# address_decoder_v1.net
KiCad netlist of a schematic drawn in EAGLE
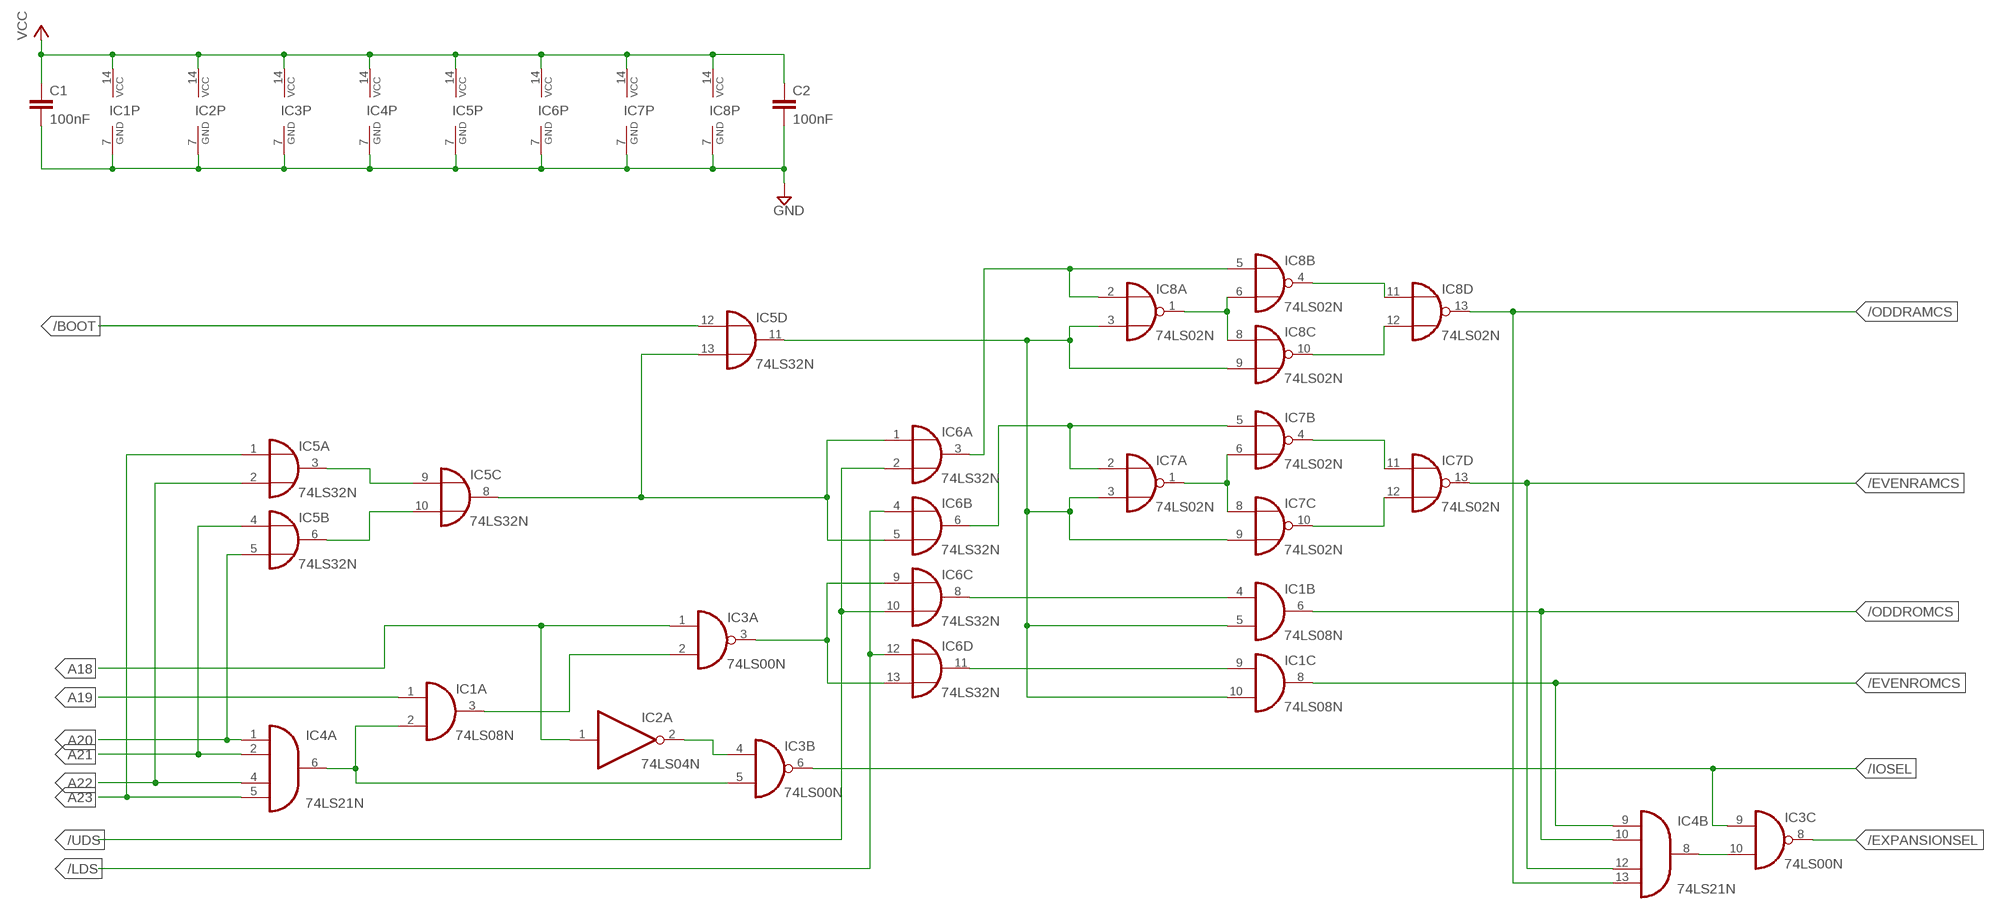
[diagram p0: schematic, sheet 1]

(export (version "E")
  (design (tool "Eeschema 10.0.6"))
  (components
    (comp (ref "C1")
      (value "100nF")
      (footprint "eagle-import:C025-024X044")
      (libsource (lib "eagle-import") (part "C-EU025-024X044"))
    )
    (comp (ref "C2")
      (value "100nF")
      (footprint "eagle-import:C025-024X044")
      (libsource (lib "eagle-import") (part "C-EU025-024X044"))
    )
    (comp (ref "IC1")
      (value "74LS08N")
      (footprint "eagle-import:DIL14")
      (libsource (lib "eagle-import") (part "7408NLS"))
    )
    (comp (ref "IC2")
      (value "74LS04N")
      (footprint "eagle-import:DIL14")
      (libsource (lib "eagle-import") (part "7404NLS"))
    )
    (comp (ref "IC3")
      (value "74LS00N")
      (footprint "eagle-import:DIL14")
      (libsource (lib "eagle-import") (part "7400NLS"))
    )
    (comp (ref "IC4")
      (value "74LS21N")
      (footprint "eagle-import:DIL14")
      (libsource (lib "eagle-import") (part "7421NLS"))
    )
    (comp (ref "IC5")
      (value "74LS32N")
      (footprint "eagle-import:DIL14")
      (libsource (lib "eagle-import") (part "7432NLS"))
    )
    (comp (ref "IC6")
      (value "74LS32N")
      (footprint "eagle-import:DIL14")
      (libsource (lib "eagle-import") (part "7432NLS"))
    )
    (comp (ref "IC7")
      (value "74LS02N")
      (footprint "eagle-import:DIL14")
      (libsource (lib "eagle-import") (part "7402NLS"))
    )
    (comp (ref "IC8")
      (value "74LS02N")
      (footprint "eagle-import:DIL14")
      (libsource (lib "eagle-import") (part "7402NLS"))
    )
  )
  (nets
    (net (code "1") (name "A18") (class "Default")
      (node (ref "IC2") (pin "1") (pinfunction "I_1") (pintype "input"))
      (node (ref "IC3") (pin "1") (pinfunction "I0_1") (pintype "input"))
    )
    (net (code "2") (name "A19") (class "Default")
      (node (ref "IC1") (pin "1") (pinfunction "I0_1") (pintype "input"))
    )
    (net (code "3") (name "A20") (class "Default")
      (node (ref "IC4") (pin "1") (pinfunction "I0_1") (pintype "input"))
      (node (ref "IC5") (pin "5") (pinfunction "I1_5") (pintype "input"))
    )
    (net (code "4") (name "A21") (class "Default")
      (node (ref "IC4") (pin "2") (pinfunction "I1_2") (pintype "input"))
      (node (ref "IC5") (pin "4") (pinfunction "I0_4") (pintype "input"))
    )
    (net (code "5") (name "A22") (class "Default")
      (node (ref "IC4") (pin "4") (pinfunction "I2_4") (pintype "input"))
      (node (ref "IC5") (pin "2") (pinfunction "I1_2") (pintype "input"))
    )
    (net (code "6") (name "A23") (class "Default")
      (node (ref "IC4") (pin "5") (pinfunction "I3_5") (pintype "input"))
      (node (ref "IC5") (pin "1") (pinfunction "I0_1") (pintype "input"))
    )
    (net (code "7") (name "GND") (class "Default")
      (node (ref "C1") (pin "2") (pinfunction "2_2") (pintype "passive"))
      (node (ref "C2") (pin "2") (pinfunction "2_2") (pintype "passive"))
      (node (ref "IC1") (pin "7") (pinfunction "GND_7") (pintype "power_in"))
      (node (ref "IC2") (pin "7") (pinfunction "GND_7") (pintype "power_in"))
      (node (ref "IC3") (pin "7") (pinfunction "GND_7") (pintype "power_in"))
      (node (ref "IC4") (pin "7") (pinfunction "GND_7") (pintype "power_in"))
      (node (ref "IC5") (pin "7") (pinfunction "GND_7") (pintype "power_in"))
      (node (ref "IC6") (pin "7") (pinfunction "GND_7") (pintype "power_in"))
      (node (ref "IC7") (pin "7") (pinfunction "GND_7") (pintype "power_in"))
      (node (ref "IC8") (pin "7") (pinfunction "GND_7") (pintype "power_in"))
    )
    (net (code "8") (name "Net-(IC1A-I1)") (class "Default")
      (node (ref "IC1") (pin "2") (pinfunction "I1_2") (pintype "input"))
      (node (ref "IC3") (pin "5") (pinfunction "I1_5") (pintype "input"))
      (node (ref "IC4") (pin "6") (pinfunction "O_6") (pintype "output"))
    )
    (net (code "9") (name "Net-(IC1A-O)") (class "Default")
      (node (ref "IC1") (pin "3") (pinfunction "O_3") (pintype "output"))
      (node (ref "IC3") (pin "2") (pinfunction "I1_2") (pintype "input"))
    )
    (net (code "10") (name "Net-(IC1B-I0)") (class "Default")
      (node (ref "IC1") (pin "4") (pinfunction "I0_4") (pintype "input"))
      (node (ref "IC6") (pin "8") (pinfunction "O_8") (pintype "output"))
    )
    (net (code "11") (name "Net-(IC1B-I1)") (class "Default")
      (node (ref "IC1") (pin "10") (pinfunction "I1_10") (pintype "input"))
      (node (ref "IC1") (pin "5") (pinfunction "I1_5") (pintype "input"))
      (node (ref "IC5") (pin "11") (pinfunction "O_11") (pintype "output"))
      (node (ref "IC7") (pin "3") (pinfunction "I1_3") (pintype "input"))
      (node (ref "IC7") (pin "9") (pinfunction "I1_9") (pintype "input"))
      (node (ref "IC8") (pin "3") (pinfunction "I1_3") (pintype "input"))
      (node (ref "IC8") (pin "9") (pinfunction "I1_9") (pintype "input"))
    )
    (net (code "12") (name "Net-(IC1C-I0)") (class "Default")
      (node (ref "IC1") (pin "9") (pinfunction "I0_9") (pintype "input"))
      (node (ref "IC6") (pin "11") (pinfunction "O_11") (pintype "output"))
    )
    (net (code "13") (name "Net-(IC2A-O)") (class "Default")
      (node (ref "IC2") (pin "2") (pinfunction "O_2") (pintype "output"))
      (node (ref "IC3") (pin "4") (pinfunction "I0_4") (pintype "input"))
    )
    (net (code "14") (name "Net-(IC3A-O)") (class "Default")
      (node (ref "IC3") (pin "3") (pinfunction "O_3") (pintype "output"))
      (node (ref "IC6") (pin "13") (pinfunction "I1_13") (pintype "input"))
      (node (ref "IC6") (pin "9") (pinfunction "I0_9") (pintype "input"))
    )
    (net (code "15") (name "Net-(IC3C-I1)") (class "Default")
      (node (ref "IC3") (pin "10") (pinfunction "I1_10") (pintype "input"))
      (node (ref "IC4") (pin "8") (pinfunction "O_8") (pintype "output"))
    )
    (net (code "16") (name "Net-(IC5A-O)") (class "Default")
      (node (ref "IC5") (pin "3") (pinfunction "O_3") (pintype "output"))
      (node (ref "IC5") (pin "9") (pinfunction "I0_9") (pintype "input"))
    )
    (net (code "17") (name "Net-(IC5B-O)") (class "Default")
      (node (ref "IC5") (pin "10") (pinfunction "I1_10") (pintype "input"))
      (node (ref "IC5") (pin "6") (pinfunction "O_6") (pintype "output"))
    )
    (net (code "18") (name "Net-(IC5C-O)") (class "Default")
      (node (ref "IC5") (pin "13") (pinfunction "I1_13") (pintype "input"))
      (node (ref "IC5") (pin "8") (pinfunction "O_8") (pintype "output"))
      (node (ref "IC6") (pin "1") (pinfunction "I0_1") (pintype "input"))
      (node (ref "IC6") (pin "5") (pinfunction "I1_5") (pintype "input"))
    )
    (net (code "19") (name "Net-(IC6A-O)") (class "Default")
      (node (ref "IC6") (pin "3") (pinfunction "O_3") (pintype "output"))
      (node (ref "IC8") (pin "2") (pinfunction "I0_2") (pintype "input"))
      (node (ref "IC8") (pin "5") (pinfunction "I0_5") (pintype "input"))
    )
    (net (code "20") (name "Net-(IC6B-O)") (class "Default")
      (node (ref "IC6") (pin "6") (pinfunction "O_6") (pintype "output"))
      (node (ref "IC7") (pin "2") (pinfunction "I0_2") (pintype "input"))
      (node (ref "IC7") (pin "5") (pinfunction "I0_5") (pintype "input"))
    )
    (net (code "21") (name "Net-(IC7A-O)") (class "Default")
      (node (ref "IC7") (pin "1") (pinfunction "O_1") (pintype "output"))
      (node (ref "IC7") (pin "6") (pinfunction "I1_6") (pintype "input"))
      (node (ref "IC7") (pin "8") (pinfunction "I0_8") (pintype "input"))
    )
    (net (code "22") (name "Net-(IC7B-O)") (class "Default")
      (node (ref "IC7") (pin "11") (pinfunction "I0_11") (pintype "input"))
      (node (ref "IC7") (pin "4") (pinfunction "O_4") (pintype "output"))
    )
    (net (code "23") (name "Net-(IC7C-O)") (class "Default")
      (node (ref "IC7") (pin "10") (pinfunction "O_10") (pintype "output"))
      (node (ref "IC7") (pin "12") (pinfunction "I1_12") (pintype "input"))
    )
    (net (code "24") (name "Net-(IC8A-O)") (class "Default")
      (node (ref "IC8") (pin "1") (pinfunction "O_1") (pintype "output"))
      (node (ref "IC8") (pin "6") (pinfunction "I1_6") (pintype "input"))
      (node (ref "IC8") (pin "8") (pinfunction "I0_8") (pintype "input"))
    )
    (net (code "25") (name "Net-(IC8B-O)") (class "Default")
      (node (ref "IC8") (pin "11") (pinfunction "I0_11") (pintype "input"))
      (node (ref "IC8") (pin "4") (pinfunction "O_4") (pintype "output"))
    )
    (net (code "26") (name "Net-(IC8C-O)") (class "Default")
      (node (ref "IC8") (pin "10") (pinfunction "O_10") (pintype "output"))
      (node (ref "IC8") (pin "12") (pinfunction "I1_12") (pintype "input"))
    )
    (net (code "27") (name "VCC") (class "Default")
      (node (ref "C1") (pin "1") (pinfunction "1_1") (pintype "passive"))
      (node (ref "C2") (pin "1") (pinfunction "1_1") (pintype "passive"))
      (node (ref "IC1") (pin "14") (pinfunction "VCC_14") (pintype "power_in"))
      (node (ref "IC2") (pin "14") (pinfunction "VCC_14") (pintype "power_in"))
      (node (ref "IC3") (pin "14") (pinfunction "VCC_14") (pintype "power_in"))
      (node (ref "IC4") (pin "14") (pinfunction "VCC_14") (pintype "power_in"))
      (node (ref "IC5") (pin "14") (pinfunction "VCC_14") (pintype "power_in"))
      (node (ref "IC6") (pin "14") (pinfunction "VCC_14") (pintype "power_in"))
      (node (ref "IC7") (pin "14") (pinfunction "VCC_14") (pintype "power_in"))
      (node (ref "IC8") (pin "14") (pinfunction "VCC_14") (pintype "power_in"))
    )
    (net (code "28") (name "{slash}BOOT") (class "Default")
      (node (ref "IC5") (pin "12") (pinfunction "I0_12") (pintype "input"))
    )
    (net (code "29") (name "{slash}EVENRAMCS") (class "Default")
      (node (ref "IC4") (pin "12") (pinfunction "I2_12") (pintype "input"))
      (node (ref "IC7") (pin "13") (pinfunction "O_13") (pintype "output"))
    )
    (net (code "30") (name "{slash}EVENROMCS") (class "Default")
      (node (ref "IC1") (pin "8") (pinfunction "O_8") (pintype "output"))
      (node (ref "IC4") (pin "9") (pinfunction "I0_9") (pintype "input"))
    )
    (net (code "31") (name "{slash}EXPANSIONSEL") (class "Default")
      (node (ref "IC3") (pin "8") (pinfunction "O_8") (pintype "output"))
    )
    (net (code "32") (name "{slash}IOSEL") (class "Default")
      (node (ref "IC3") (pin "6") (pinfunction "O_6") (pintype "output"))
      (node (ref "IC3") (pin "9") (pinfunction "I0_9") (pintype "input"))
    )
    (net (code "33") (name "{slash}LDS") (class "Default")
      (node (ref "IC6") (pin "12") (pinfunction "I0_12") (pintype "input"))
      (node (ref "IC6") (pin "4") (pinfunction "I0_4") (pintype "input"))
    )
    (net (code "34") (name "{slash}ODDRAMCS") (class "Default")
      (node (ref "IC4") (pin "13") (pinfunction "I3_13") (pintype "input"))
      (node (ref "IC8") (pin "13") (pinfunction "O_13") (pintype "output"))
    )
    (net (code "35") (name "{slash}ODDROMCS") (class "Default")
      (node (ref "IC1") (pin "6") (pinfunction "O_6") (pintype "output"))
      (node (ref "IC4") (pin "10") (pinfunction "I1_10") (pintype "input"))
    )
    (net (code "36") (name "{slash}UDS") (class "Default")
      (node (ref "IC6") (pin "10") (pinfunction "I1_10") (pintype "input"))
      (node (ref "IC6") (pin "2") (pinfunction "I1_2") (pintype "input"))
    )
  )
)
